# Schematic2.net
KiCad netlist of a schematic drawn in Altium Designer
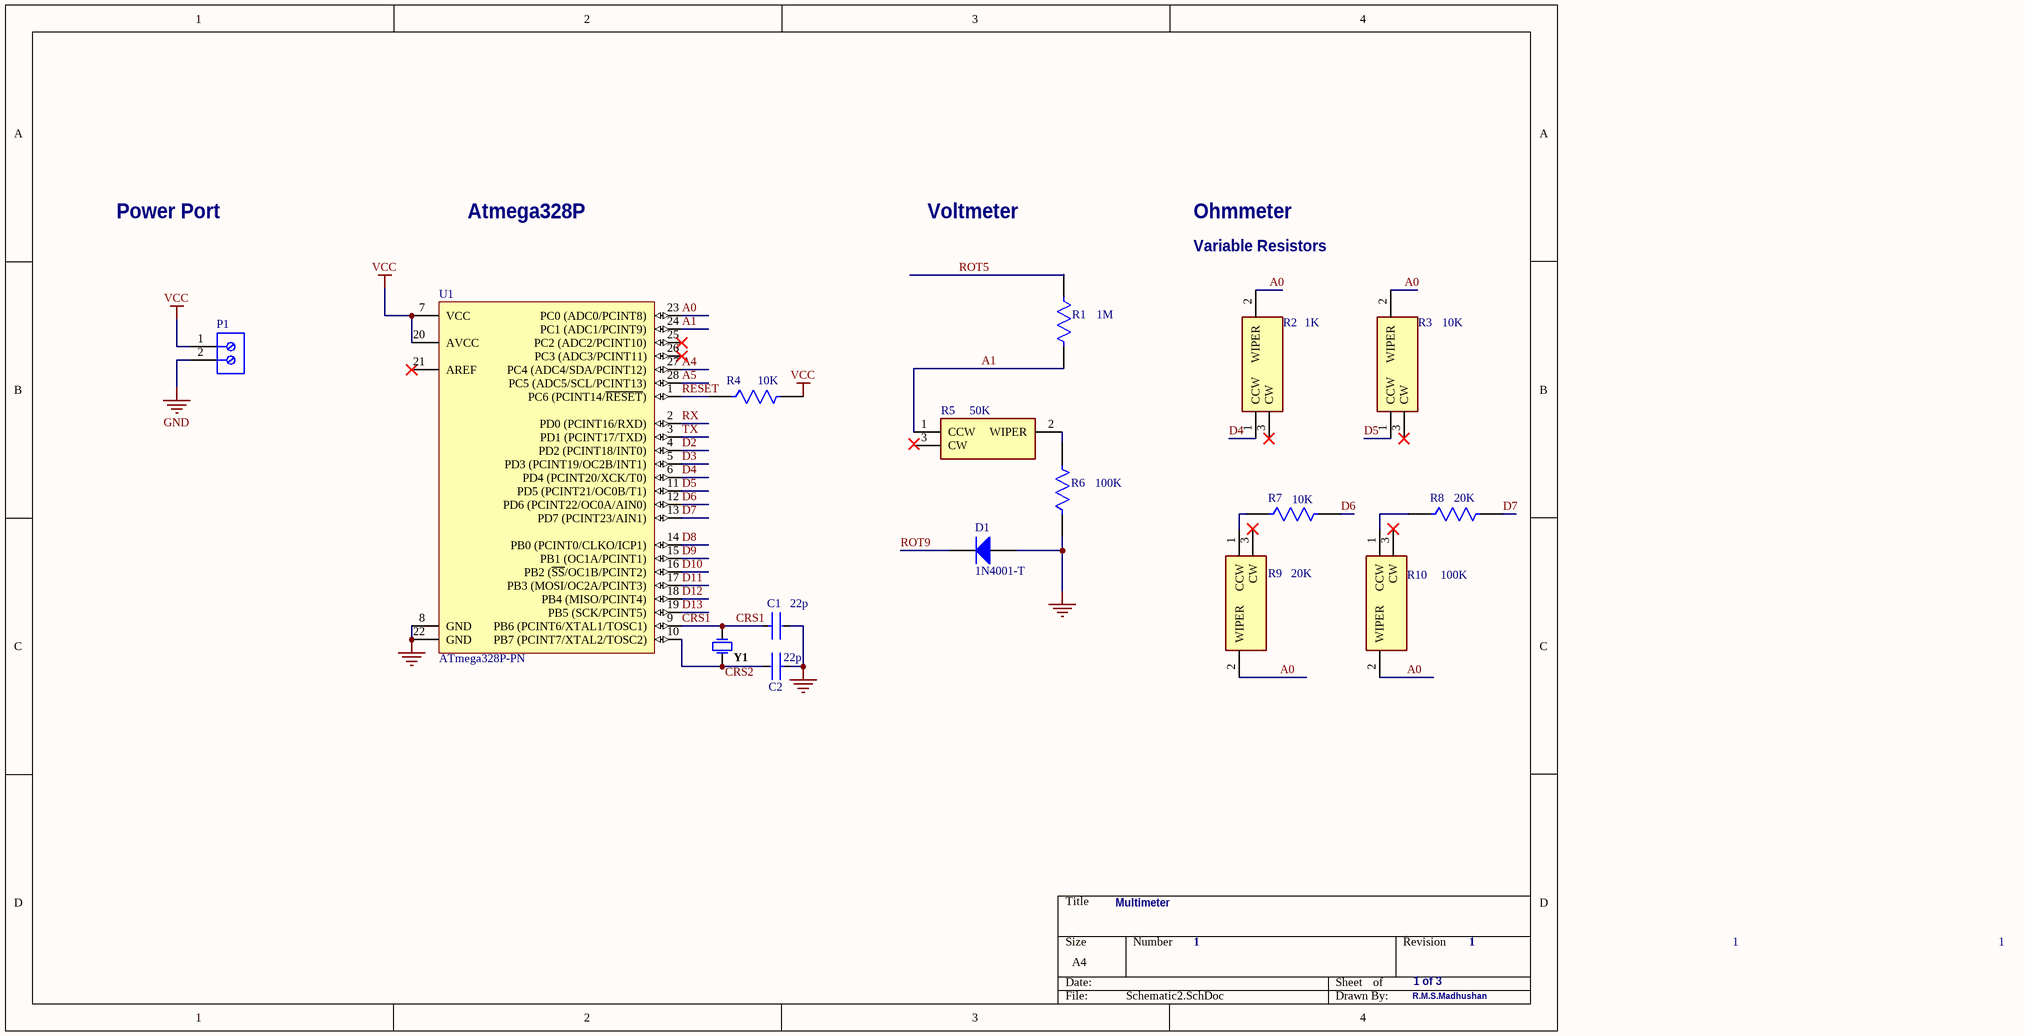
[diagram p0: Schematic2.SchDoc]

(export (version "E")
  (design (tool "Eeschema 10.0.6"))
  (components
    (comp (ref "C1")
      (value "22p")
      (footprint "FP-RDE0M1-MFG")
      (description "Ceramic Capacitor 22pF ±5% 50V C0G Radial")
      (fields (field (name "TOLERANCE") "5%"))
      (libsource (lib "Altium Content Vault") (part "b4654b650e69147ec39a6b967a45e02"))
    )
    (comp (ref "C2")
      (value "22p")
      (footprint "FP-RDE0M1-MFG")
      (description "Ceramic Capacitor 22pF ±5% 50V C0G Radial")
      (fields (field (name "TOLERANCE") "5%"))
      (libsource (lib "Altium Content Vault") (part "b4654b650e69147ec39a6b967a45e02"))
    )
    (comp (ref "D1")
      (value "1N4001-T")
      (footprint "DIOD-DO-41-P-2_V")
      (description "1.0 A Rectifier, 15 pF, 50 V, -65 to 150 degC, 2-Pin DO-41 Plastic, RoHS, Tape and Reel")
      (fields (field (name "MANUFACTURER") "Diodes Inc"))
      (libsource (lib "Altium Content Vault") (part "DIOD-D-A1K2-2"))
    )
    (comp (ref "P1")
      (value "691214110002")
      (footprint "691214110002")
      (description "Serie 2141 - 3.50 mm Horizontal Entry Modular with Rising Cage Clamp WR-TBL, 2 pin")
      (fields (field (name "MANUFACTURER") "Wurth Elektronik") (field (name "PUBLISHER") "WurthElektronik"))
      (libsource (lib "Altium Content Vault") (part "WE-CN-1P-F-TB2"))
    )
    (comp (ref "R1")
      (value "1M")
      (footprint "FP-G001R1000FE1280-MFG")
      (description "Res Wirewound 0.1 Ohm 1% 1W ±90ppm/°C Ceramic Hi Temp Sil AXL Thru-Hole Bulk")
      (fields (field (name "TOLERANCE") "1%"))
      (libsource (lib "Altium Content Vault") (part "1029c3af85768c4190bb7ad29bc67b5"))
    )
    (comp (ref "R2")
      (value "1K")
      (footprint "SamacSys:3362P_1")
      (description "Resistor")
      (fields
        (field (name "MANUFACTURER_PART_NUMBER") "3362P-1-203LF")
        (field (name "MOUSER PART NUMBER") "652-3362P-1-203LF")
      )
      (libsource (lib "") (part "3362P-1-203LF_1"))
    )
    (comp (ref "R3")
      (value "10K")
      (footprint "SamacSys:3362P_1")
      (description "Resistor")
      (fields
        (field (name "MANUFACTURER_PART_NUMBER") "3362P-1-203LF")
        (field (name "MOUSER PART NUMBER") "652-3362P-1-203LF")
      )
      (libsource (lib "") (part "3362P-1-203LF_1"))
    )
    (comp (ref "R4")
      (value "10K")
      (footprint "FP-G001R1000FE1280-MFG")
      (description "Res Wirewound 0.1 Ohm 1% 1W ±90ppm/°C Ceramic Hi Temp Sil AXL Thru-Hole Bulk")
      (fields (field (name "TOLERANCE") "1%"))
      (libsource (lib "Altium Content Vault") (part "1029c3af85768c4190bb7ad29bc67b5"))
    )
    (comp (ref "R5")
      (value "50K")
      (footprint "SamacSys:3362P_1")
      (description "Resistor")
      (fields
        (field (name "MANUFACTURER_PART_NUMBER") "3362P-1-203LF")
        (field (name "MOUSER PART NUMBER") "652-3362P-1-203LF")
      )
      (libsource (lib "*") (part "3362P-1-203LF"))
    )
    (comp (ref "R6")
      (value "100K")
      (footprint "FP-G001R1000FE1280-MFG")
      (description "Res Wirewound 0.1 Ohm 1% 1W ±90ppm/°C Ceramic Hi Temp Sil AXL Thru-Hole Bulk")
      (fields (field (name "TOLERANCE") "1%"))
      (libsource (lib "Altium Content Vault") (part "1029c3af85768c4190bb7ad29bc67b5"))
    )
    (comp (ref "R7")
      (value "10K")
      (footprint "FP-G001R1000FE1280-MFG")
      (description "Res Wirewound 0.1 Ohm 1% 1W ±90ppm/°C Ceramic Hi Temp Sil AXL Thru-Hole Bulk")
      (fields (field (name "TOLERANCE") "1%"))
      (libsource (lib "Altium Content Vault") (part "1029c3af85768c4190bb7ad29bc67b5"))
    )
    (comp (ref "R8")
      (value "20K")
      (footprint "FP-G001R1000FE1280-MFG")
      (description "Res Wirewound 0.1 Ohm 1% 1W ±90ppm/°C Ceramic Hi Temp Sil AXL Thru-Hole Bulk")
      (fields (field (name "TOLERANCE") "1%"))
      (libsource (lib "Altium Content Vault") (part "1029c3af85768c4190bb7ad29bc67b5"))
    )
    (comp (ref "R9")
      (value "20K")
      (footprint "SamacSys:3362P_1")
      (description "Resistor")
      (fields
        (field (name "MANUFACTURER_PART_NUMBER") "3362P-1-203LF")
        (field (name "MOUSER PART NUMBER") "652-3362P-1-203LF")
      )
      (libsource (lib "") (part "3362P-1-203LF_2"))
    )
    (comp (ref "R10")
      (value "100K")
      (footprint "SamacSys:3362P_1")
      (description "Resistor")
      (fields
        (field (name "MANUFACTURER_PART_NUMBER") "3362P-1-203LF")
        (field (name "MOUSER PART NUMBER") "652-3362P-1-203LF")
      )
      (libsource (lib "") (part "3362P-1-203LF_2"))
    )
    (comp (ref "U1")
      (value "ATmega328P-PN")
      (footprint "28P3")
      (libsource (lib "Altium Content Vault") (part "MC-8B-ATM48-IL28"))
    )
    (comp (ref "Y1")
      (value "FOXSLF/160-20")
      (footprint "FOX-FOXSLF160-20")
      (description "Resistance Weld Thru-Hole Crystal, 16 MHz, -20 to 70 degC, 2-Pin THD, RoHS, Bulk")
      (fields (field (name "TOLERANCE") "1%"))
      (libsource (lib "Altium Content Vault") (part "XTAL-1-2-2"))
    )
  )
  (nets
    (net (code "2") (name "/A0") (class "Default")
      (node (ref "R10") (pin "2") (pinfunction "WIPER_2") (pintype "passive"))
      (node (ref "R2") (pin "2") (pinfunction "WIPER_2") (pintype "passive"))
      (node (ref "R3") (pin "2") (pinfunction "WIPER_2") (pintype "passive"))
      (node (ref "R9") (pin "2") (pinfunction "WIPER_2") (pintype "passive"))
      (node (ref "U1") (pin "23") (pinfunction "PC0_(ADC0/PCINT8)_23") (pintype "bidirectional"))
    )
    (net (code "3") (name "/A1") (class "Default")
      (node (ref "R1") (pin "2") (pinfunction "2_2") (pintype "passive"))
      (node (ref "R5") (pin "1") (pinfunction "CCW_1") (pintype "passive"))
      (node (ref "U1") (pin "24") (pinfunction "PC1_(ADC1/PCINT9)_24") (pintype "bidirectional"))
    )
    (net (code "4") (name "/A4") (class "Default")
      (node (ref "U1") (pin "27") (pinfunction "PC4_(ADC4/SDA/PCINT12)_27") (pintype "bidirectional"))
    )
    (net (code "5") (name "/A5") (class "Default")
      (node (ref "U1") (pin "28") (pinfunction "PC5_(ADC5/SCL/PCINT13)_28") (pintype "bidirectional"))
    )
    (net (code "6") (name "/CRS1") (class "Default")
      (node (ref "C1") (pin "1") (pinfunction "1_1") (pintype "passive"))
      (node (ref "U1") (pin "9") (pinfunction "PB6_(PCINT6/XTAL1/TOSC1)_9") (pintype "bidirectional"))
      (node (ref "Y1") (pin "1") (pinfunction "1_1") (pintype "passive"))
    )
    (net (code "8") (name "/D2") (class "Default")
      (node (ref "U1") (pin "4") (pinfunction "PD2_(PCINT18/INT0)_4") (pintype "bidirectional"))
    )
    (net (code "9") (name "/D3") (class "Default")
      (node (ref "U1") (pin "5") (pinfunction "PD3_(PCINT19/OC2B/INT1)_5") (pintype "bidirectional"))
    )
    (net (code "10") (name "/D4") (class "Default")
      (node (ref "R2") (pin "1") (pinfunction "CCW_1") (pintype "passive"))
      (node (ref "U1") (pin "6") (pinfunction "PD4_(PCINT20/XCK/T0)_6") (pintype "bidirectional"))
    )
    (net (code "11") (name "/D5") (class "Default")
      (node (ref "R3") (pin "1") (pinfunction "CCW_1") (pintype "passive"))
      (node (ref "U1") (pin "11") (pinfunction "PD5_(PCINT21/OC0B/T1)_11") (pintype "bidirectional"))
    )
    (net (code "12") (name "/D6") (class "Default")
      (node (ref "R7") (pin "2") (pinfunction "2_2") (pintype "passive"))
      (node (ref "U1") (pin "12") (pinfunction "PD6_(PCINT22/OC0A/AIN0)_12") (pintype "bidirectional"))
    )
    (net (code "13") (name "/D7") (class "Default")
      (node (ref "R8") (pin "2") (pinfunction "2_2") (pintype "passive"))
      (node (ref "U1") (pin "13") (pinfunction "PD7_(PCINT23/AIN1)_13") (pintype "bidirectional"))
    )
    (net (code "14") (name "/D8") (class "Default")
      (node (ref "U1") (pin "14") (pinfunction "PB0_(PCINT0/CLKO/ICP1)_14") (pintype "bidirectional"))
    )
    (net (code "15") (name "/D9") (class "Default")
      (node (ref "U1") (pin "15") (pinfunction "PB1_(OC1A/PCINT1)_15") (pintype "bidirectional"))
    )
    (net (code "16") (name "/D10") (class "Default")
      (node (ref "U1") (pin "16") (pinfunction "PB2_(~{SS}/OC1B/PCINT2)_16") (pintype "bidirectional"))
    )
    (net (code "17") (name "/D11") (class "Default")
      (node (ref "U1") (pin "17") (pinfunction "PB3_(MOSI/OC2A/PCINT3)_17") (pintype "bidirectional"))
    )
    (net (code "18") (name "/D12") (class "Default")
      (node (ref "U1") (pin "18") (pinfunction "PB4_(MISO/PCINT4)_18") (pintype "bidirectional"))
    )
    (net (code "19") (name "/D13") (class "Default")
      (node (ref "U1") (pin "19") (pinfunction "PB5_(SCK/PCINT5)_19") (pintype "bidirectional"))
    )
    (net (code "20") (name "/RESET") (class "Default")
      (node (ref "R4") (pin "1") (pinfunction "1_1") (pintype "passive"))
      (node (ref "U1") (pin "1") (pinfunction "PC6_(PCINT14/~{RESET})_1") (pintype "bidirectional"))
    )
    (net (code "21") (name "/ROT5") (class "Default")
      (node (ref "R1") (pin "1") (pinfunction "1_1") (pintype "passive"))
    )
    (net (code "22") (name "/ROT9") (class "Default")
      (node (ref "D1") (pin "2") (pinfunction "K_2") (pintype "passive"))
    )
    (net (code "23") (name "/RX") (class "Default")
      (node (ref "U1") (pin "2") (pinfunction "PD0_(PCINT16/RXD)_2") (pintype "bidirectional"))
    )
    (net (code "24") (name "/TX") (class "Default")
      (node (ref "U1") (pin "3") (pinfunction "PD1_(PCINT17/TXD)_3") (pintype "bidirectional"))
    )
    (net (code "25") (name "GND") (class "Default")
      (node (ref "C1") (pin "2") (pinfunction "2_2") (pintype "passive"))
      (node (ref "C2") (pin "1") (pinfunction "1_1") (pintype "passive"))
      (node (ref "D1") (pin "1") (pinfunction "A_1") (pintype "passive"))
      (node (ref "P1") (pin "2") (pinfunction "2_2") (pintype "passive"))
      (node (ref "R6") (pin "1") (pinfunction "1_1") (pintype "passive"))
      (node (ref "U1") (pin "22") (pinfunction "GND_22") (pintype "power_in"))
      (node (ref "U1") (pin "8") (pinfunction "GND_8") (pintype "power_in"))
    )
    (net (code "26") (name "Net-(R5-WIPER)") (class "Default")
      (node (ref "R5") (pin "2") (pinfunction "WIPER_2") (pintype "passive"))
      (node (ref "R6") (pin "2") (pinfunction "2_2") (pintype "passive"))
    )
    (net (code "27") (name "Net-(R9-CCW)") (class "Default")
      (node (ref "R7") (pin "1") (pinfunction "1_1") (pintype "passive"))
      (node (ref "R9") (pin "1") (pinfunction "CCW_1") (pintype "passive"))
    )
    (net (code "28") (name "Net-(R10-CCW)") (class "Default")
      (node (ref "R10") (pin "1") (pinfunction "CCW_1") (pintype "passive"))
      (node (ref "R8") (pin "1") (pinfunction "1_1") (pintype "passive"))
    )
    (net (code "29") (name "Net-(U1-PB7_(PCINT7{slash}XTAL2{slash}TOSC2))") (class "Default")
      (node (ref "C2") (pin "2") (pinfunction "2_2") (pintype "passive"))
      (node (ref "U1") (pin "10") (pinfunction "PB7_(PCINT7/XTAL2/TOSC2)_10") (pintype "bidirectional"))
      (node (ref "Y1") (pin "2") (pinfunction "2_2") (pintype "passive"))
    )
    (net (code "30") (name "VCC") (class "Default")
      (node (ref "P1") (pin "1") (pinfunction "1_1") (pintype "passive"))
      (node (ref "R4") (pin "2") (pinfunction "2_2") (pintype "passive"))
      (node (ref "U1") (pin "20") (pinfunction "AVCC_20") (pintype "power_in"))
      (node (ref "U1") (pin "7") (pinfunction "VCC_7") (pintype "power_in"))
    )
    (net (code "31") (name "unconnected-(R2-CW-Pad3)") (class "Default")
      (node (ref "R2") (pin "3") (pinfunction "CW_3") (pintype "passive+no_connect"))
    )
    (net (code "32") (name "unconnected-(R3-CW-Pad3)") (class "Default")
      (node (ref "R3") (pin "3") (pinfunction "CW_3") (pintype "passive+no_connect"))
    )
    (net (code "33") (name "unconnected-(R5-CW-Pad3)") (class "Default")
      (node (ref "R5") (pin "3") (pinfunction "CW_3") (pintype "passive"))
    )
    (net (code "34") (name "unconnected-(R9-CW-Pad3)") (class "Default")
      (node (ref "R9") (pin "3") (pinfunction "CW_3") (pintype "passive+no_connect"))
    )
    (net (code "35") (name "unconnected-(R10-CW-Pad3)") (class "Default")
      (node (ref "R10") (pin "3") (pinfunction "CW_3") (pintype "passive+no_connect"))
    )
    (net (code "36") (name "unconnected-(U1-AREF-Pad21)") (class "Default")
      (node (ref "U1") (pin "21") (pinfunction "AREF_21") (pintype "power_in+no_connect"))
    )
    (net (code "37") (name "unconnected-(U1-PC2_(ADC2{slash}PCINT10)-Pad25)") (class "Default")
      (node (ref "U1") (pin "25") (pinfunction "PC2_(ADC2/PCINT10)_25") (pintype "bidirectional+no_connect"))
    )
    (net (code "38") (name "unconnected-(U1-PC3_(ADC3{slash}PCINT11)-Pad26)") (class "Default")
      (node (ref "U1") (pin "26") (pinfunction "PC3_(ADC3/PCINT11)_26") (pintype "bidirectional+no_connect"))
    )
  )
)
